# HandlebarTouchFPCB_v1_1.net
KiCad netlist of a schematic drawn in Altium Designer
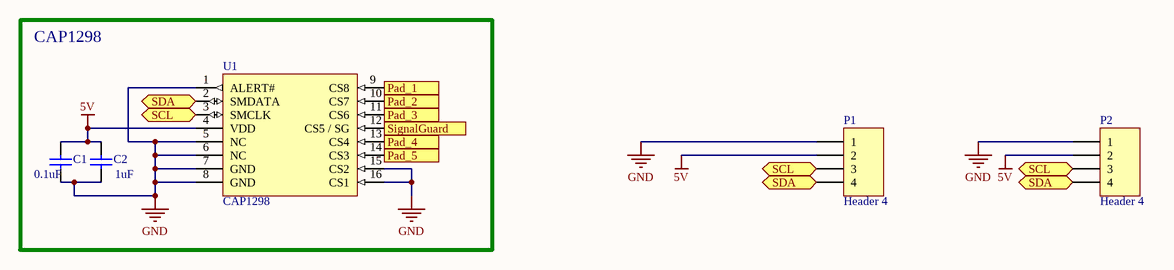
[diagram p0: HandlebarTouchFPCB_v1.1.SchDoc]

(export (version "E")
  (design (tool "Eeschema 10.0.6"))
  (components
    (comp (ref "C1")
      (value "0.1uF")
      (footprint "CAP 0805 b")
      (description "YAGEO (PHYCOMP)  CC0805KRX7R8BB104  COND, CERÁ MULT, X7R, 100NF, 25V, 0805")
      (fields (field (name "Comment") "Cap") (field (name "PUBLISHER") "Altium Limited"))
      (libsource (lib "Miscellaneous Devices") (part "Cap Semi"))
    )
    (comp (ref "C2")
      (value "1uF")
      (footprint "CAP 0805 b")
      (description "TAIYO YUDEN  TMK212BJ105KG-T  COND, CERÁ MULT, X5R, 1UF, 25V, 0805")
      (fields (field (name "Comment") "Cap") (field (name "PUBLISHER") "Altium Limited"))
      (libsource (lib "Miscellaneous Devices") (part "Cap Semi"))
    )
    (comp (ref "P1")
      (value "Header 4")
      (footprint "FPCB_4_Connector")
      (description "Header, 4-Pin")
      (fields (field (name "PUBLISHER") "Altium Limited"))
      (libsource (lib "Miscellaneous Connectors") (part "Header 4"))
    )
    (comp (ref "P2")
      (value "Header 4")
      (footprint "4PAD_CONNECTOR_SHORT")
      (description "Header, 4-Pin")
      (fields (field (name "PUBLISHER") "Altium Limited"))
      (libsource (lib "Miscellaneous Connectors") (part "Header 4"))
    )
    (comp (ref "U1")
      (value "CAP1298")
      (footprint "QFN-COL 16 (3x3)  V2")
      (libsource (lib "Libreria_Alex") (part "CAP1298"))
    )
  )
  (nets
    (net (code "1") (name "/Pad_1") (class "Default")
      (node (ref "U1") (pin "9") (pinfunction "CS8_9") (pintype "input"))
    )
    (net (code "2") (name "/Pad_2") (class "Default")
      (node (ref "U1") (pin "10") (pinfunction "CS7_10") (pintype "input"))
    )
    (net (code "3") (name "/Pad_3") (class "Default")
      (node (ref "U1") (pin "11") (pinfunction "CS6_11") (pintype "input"))
    )
    (net (code "4") (name "/Pad_4") (class "Default")
      (node (ref "U1") (pin "13") (pinfunction "CS4_13") (pintype "input"))
    )
    (net (code "5") (name "/Pad_5") (class "Default")
      (node (ref "U1") (pin "14") (pinfunction "CS3_14") (pintype "input"))
    )
    (net (code "6") (name "/SCL") (class "Default")
      (node (ref "P1") (pin "3") (pinfunction "3_3") (pintype "passive"))
      (node (ref "P2") (pin "3") (pinfunction "3_3") (pintype "passive"))
      (node (ref "U1") (pin "3") (pinfunction "SMCLK_3") (pintype "bidirectional"))
    )
    (net (code "7") (name "/SDA") (class "Default")
      (node (ref "P1") (pin "4") (pinfunction "4_4") (pintype "passive"))
      (node (ref "P2") (pin "4") (pinfunction "4_4") (pintype "passive"))
      (node (ref "U1") (pin "2") (pinfunction "SMDATA_2") (pintype "bidirectional"))
    )
    (net (code "8") (name "/SignalGuard") (class "Default")
      (node (ref "U1") (pin "12") (pinfunction "CS5_/_SG_12") (pintype "input"))
    )
    (net (code "9") (name "5V") (class "Default")
      (node (ref "C1") (pin "2") (pinfunction "2_2") (pintype "passive"))
      (node (ref "C2") (pin "2") (pinfunction "2_2") (pintype "passive"))
      (node (ref "P1") (pin "2") (pinfunction "2_2") (pintype "passive"))
      (node (ref "P2") (pin "2") (pinfunction "2_2") (pintype "passive"))
      (node (ref "U1") (pin "4") (pinfunction "VDD_4") (pintype "power_in"))
    )
    (net (code "10") (name "GND") (class "Default")
      (node (ref "C1") (pin "1") (pinfunction "1_1") (pintype "passive"))
      (node (ref "C2") (pin "1") (pinfunction "1_1") (pintype "passive"))
      (node (ref "P1") (pin "1") (pinfunction "1_1") (pintype "passive"))
      (node (ref "P2") (pin "1") (pinfunction "1_1") (pintype "passive"))
      (node (ref "U1") (pin "1") (pinfunction "ALERT#_1") (pintype "output"))
      (node (ref "U1") (pin "15") (pinfunction "CS2_15") (pintype "input"))
      (node (ref "U1") (pin "16") (pinfunction "CS1_16") (pintype "input"))
      (node (ref "U1") (pin "5") (pinfunction "NC_5") (pintype "power_in"))
      (node (ref "U1") (pin "6") (pinfunction "NC_6") (pintype "power_in"))
      (node (ref "U1") (pin "7") (pinfunction "GND_7") (pintype "power_in"))
      (node (ref "U1") (pin "8") (pinfunction "GND_8") (pintype "power_in"))
    )
  )
)
